# ep4ce30_c.net
KiCad netlist of a schematic drawn in Altium Designer
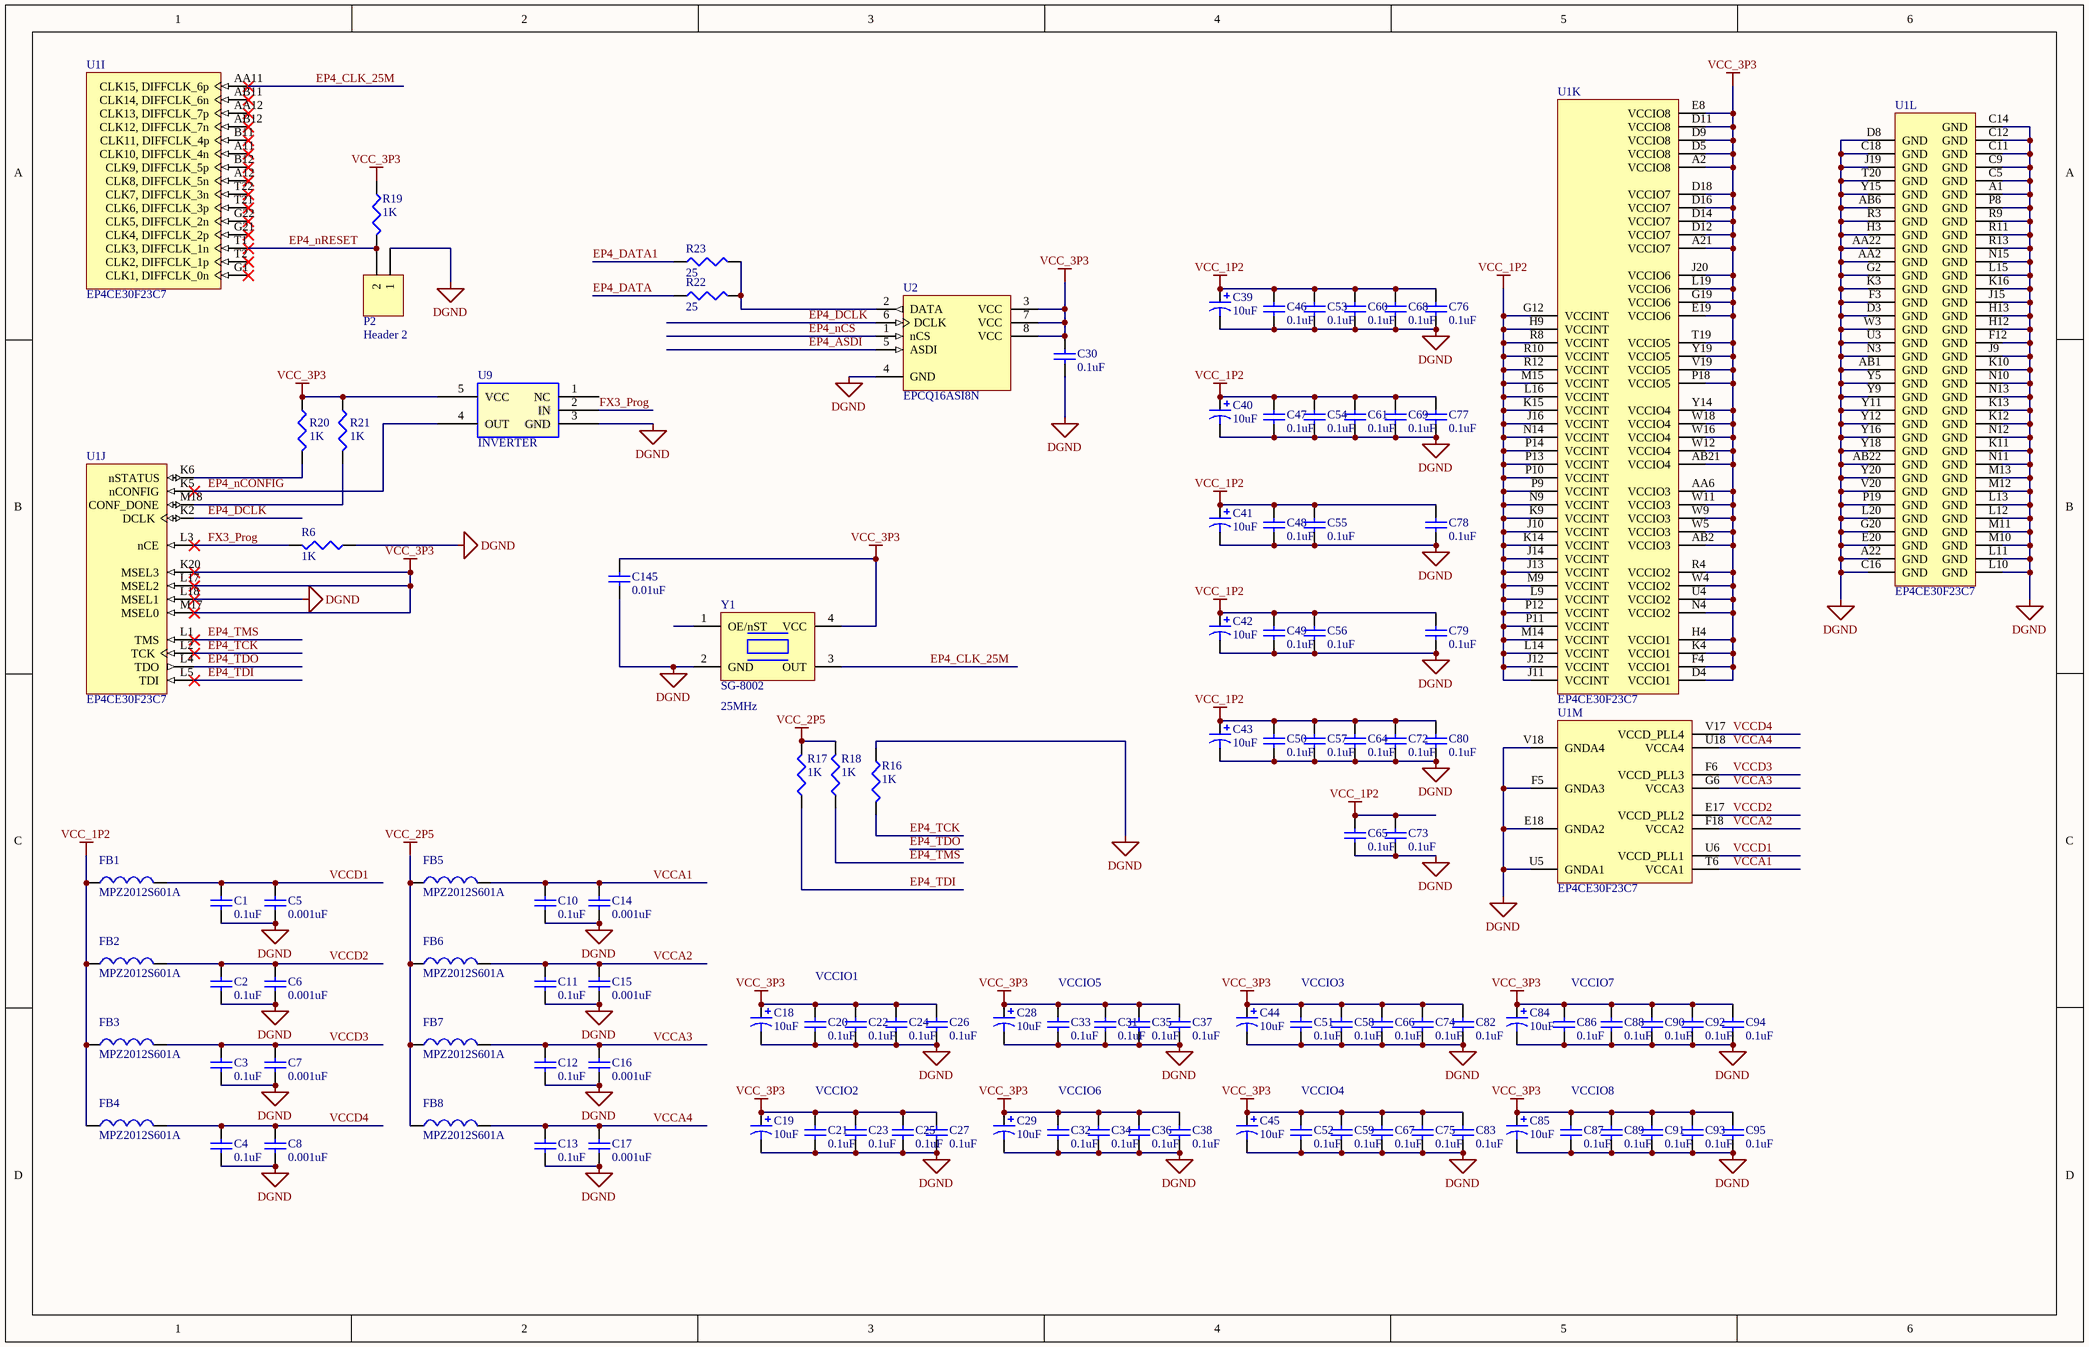
[diagram p0: ep4ce30_c.SchDoc]

(export (version "E")
  (design (tool "Eeschema 10.0.6"))
  (components
    (comp (ref "C1")
      (value "0.1uF")
      (footprint "C_0402")
      (description "Capacitor (Semiconductor SIM Model)")
      (fields (field (name "Comment") "Capacitor") (field (name "PUBLISHER") "Altium Limited"))
      (libsource (lib "Miscellaneous Devices") (part "Cap Semi"))
    )
    (comp (ref "C2")
      (value "0.1uF")
      (footprint "C_0402")
      (description "Capacitor (Semiconductor SIM Model)")
      (fields (field (name "Comment") "Capacitor") (field (name "PUBLISHER") "Altium Limited"))
      (libsource (lib "Miscellaneous Devices") (part "Cap Semi"))
    )
    (comp (ref "C3")
      (value "0.1uF")
      (footprint "C_0402")
      (description "Capacitor (Semiconductor SIM Model)")
      (fields (field (name "Comment") "Capacitor") (field (name "PUBLISHER") "Altium Limited"))
      (libsource (lib "Miscellaneous Devices") (part "Cap Semi"))
    )
    (comp (ref "C4")
      (value "0.1uF")
      (footprint "C_0402")
      (description "Capacitor (Semiconductor SIM Model)")
      (fields (field (name "Comment") "Capacitor") (field (name "PUBLISHER") "Altium Limited"))
      (libsource (lib "Miscellaneous Devices") (part "Cap Semi"))
    )
    (comp (ref "C5")
      (value "0.001uF")
      (footprint "C_0402")
      (description "Capacitor (Semiconductor SIM Model)")
      (fields (field (name "Comment") "Capacitor") (field (name "PUBLISHER") "Altium Limited"))
      (libsource (lib "Miscellaneous Devices") (part "Cap Semi"))
    )
    (comp (ref "C6")
      (value "0.001uF")
      (footprint "C_0402")
      (description "Capacitor (Semiconductor SIM Model)")
      (fields (field (name "Comment") "Capacitor") (field (name "PUBLISHER") "Altium Limited"))
      (libsource (lib "Miscellaneous Devices") (part "Cap Semi"))
    )
    (comp (ref "C7")
      (value "0.001uF")
      (footprint "C_0402")
      (description "Capacitor (Semiconductor SIM Model)")
      (fields (field (name "Comment") "Capacitor") (field (name "PUBLISHER") "Altium Limited"))
      (libsource (lib "Miscellaneous Devices") (part "Cap Semi"))
    )
    (comp (ref "C8")
      (value "0.001uF")
      (footprint "C_0402")
      (description "Capacitor (Semiconductor SIM Model)")
      (fields (field (name "Comment") "Capacitor") (field (name "PUBLISHER") "Altium Limited"))
      (libsource (lib "Miscellaneous Devices") (part "Cap Semi"))
    )
    (comp (ref "C10")
      (value "0.1uF")
      (footprint "C_0402")
      (description "Capacitor (Semiconductor SIM Model)")
      (fields (field (name "Comment") "Capacitor") (field (name "PUBLISHER") "Altium Limited"))
      (libsource (lib "Miscellaneous Devices") (part "Cap Semi"))
    )
    (comp (ref "C11")
      (value "0.1uF")
      (footprint "C_0402")
      (description "Capacitor (Semiconductor SIM Model)")
      (fields (field (name "Comment") "Capacitor") (field (name "PUBLISHER") "Altium Limited"))
      (libsource (lib "Miscellaneous Devices") (part "Cap Semi"))
    )
    (comp (ref "C12")
      (value "0.1uF")
      (footprint "C_0402")
      (description "Capacitor (Semiconductor SIM Model)")
      (fields (field (name "Comment") "Capacitor") (field (name "PUBLISHER") "Altium Limited"))
      (libsource (lib "Miscellaneous Devices") (part "Cap Semi"))
    )
    (comp (ref "C13")
      (value "0.1uF")
      (footprint "C_0402")
      (description "Capacitor (Semiconductor SIM Model)")
      (fields (field (name "Comment") "Capacitor") (field (name "PUBLISHER") "Altium Limited"))
      (libsource (lib "Miscellaneous Devices") (part "Cap Semi"))
    )
    (comp (ref "C14")
      (value "0.001uF")
      (footprint "C_0402")
      (description "Capacitor (Semiconductor SIM Model)")
      (fields (field (name "Comment") "Capacitor") (field (name "PUBLISHER") "Altium Limited"))
      (libsource (lib "Miscellaneous Devices") (part "Cap Semi"))
    )
    (comp (ref "C15")
      (value "0.001uF")
      (footprint "C_0402")
      (description "Capacitor (Semiconductor SIM Model)")
      (fields (field (name "Comment") "Capacitor") (field (name "PUBLISHER") "Altium Limited"))
      (libsource (lib "Miscellaneous Devices") (part "Cap Semi"))
    )
    (comp (ref "C16")
      (value "0.001uF")
      (footprint "C_0402")
      (description "Capacitor (Semiconductor SIM Model)")
      (fields (field (name "Comment") "Capacitor") (field (name "PUBLISHER") "Altium Limited"))
      (libsource (lib "Miscellaneous Devices") (part "Cap Semi"))
    )
    (comp (ref "C17")
      (value "0.001uF")
      (footprint "C_0402")
      (description "Capacitor (Semiconductor SIM Model)")
      (fields (field (name "Comment") "Capacitor") (field (name "PUBLISHER") "Altium Limited"))
      (libsource (lib "Miscellaneous Devices") (part "Cap Semi"))
    )
    (comp (ref "C18")
      (value "10uF")
      (footprint "CAP_B")
      (description "Polarized Capacitor (Surface Mount)")
      (fields (field (name "Comment") "Polarized Capacitor") (field (name "PUBLISHER") "Altium Limited"))
      (libsource (lib "Miscellaneous Devices") (part "Cap Pol3"))
    )
    (comp (ref "C19")
      (value "10uF")
      (footprint "CAP_B")
      (description "Polarized Capacitor (Surface Mount)")
      (fields (field (name "Comment") "Polarized Capacitor") (field (name "PUBLISHER") "Altium Limited"))
      (libsource (lib "Miscellaneous Devices") (part "Cap Pol3"))
    )
    (comp (ref "C20")
      (value "0.1uF")
      (footprint "C_0402")
      (description "Capacitor (Semiconductor SIM Model)")
      (fields (field (name "Comment") "Capacitor") (field (name "PUBLISHER") "Altium Limited"))
      (libsource (lib "Miscellaneous Devices") (part "Cap Semi"))
    )
    (comp (ref "C21")
      (value "0.1uF")
      (footprint "C_0402")
      (description "Capacitor (Semiconductor SIM Model)")
      (fields (field (name "Comment") "Capacitor") (field (name "PUBLISHER") "Altium Limited"))
      (libsource (lib "Miscellaneous Devices") (part "Cap Semi"))
    )
    (comp (ref "C22")
      (value "0.1uF")
      (footprint "C_0402")
      (description "Capacitor (Semiconductor SIM Model)")
      (fields (field (name "Comment") "Capacitor") (field (name "PUBLISHER") "Altium Limited"))
      (libsource (lib "Miscellaneous Devices") (part "Cap Semi"))
    )
    (comp (ref "C23")
      (value "0.1uF")
      (footprint "C_0402")
      (description "Capacitor (Semiconductor SIM Model)")
      (fields (field (name "Comment") "Capacitor") (field (name "PUBLISHER") "Altium Limited"))
      (libsource (lib "Miscellaneous Devices") (part "Cap Semi"))
    )
    (comp (ref "C24")
      (value "0.1uF")
      (footprint "C_0402")
      (description "Capacitor (Semiconductor SIM Model)")
      (fields (field (name "Comment") "Capacitor") (field (name "PUBLISHER") "Altium Limited"))
      (libsource (lib "Miscellaneous Devices") (part "Cap Semi"))
    )
    (comp (ref "C25")
      (value "0.1uF")
      (footprint "C_0402")
      (description "Capacitor (Semiconductor SIM Model)")
      (fields (field (name "Comment") "Capacitor") (field (name "PUBLISHER") "Altium Limited"))
      (libsource (lib "Miscellaneous Devices") (part "Cap Semi"))
    )
    (comp (ref "C26")
      (value "0.1uF")
      (footprint "C_0402")
      (description "Capacitor (Semiconductor SIM Model)")
      (fields (field (name "Comment") "Capacitor") (field (name "PUBLISHER") "Altium Limited"))
      (libsource (lib "Miscellaneous Devices") (part "Cap Semi"))
    )
    (comp (ref "C27")
      (value "0.1uF")
      (footprint "C_0402")
      (description "Capacitor (Semiconductor SIM Model)")
      (fields (field (name "Comment") "Capacitor") (field (name "PUBLISHER") "Altium Limited"))
      (libsource (lib "Miscellaneous Devices") (part "Cap Semi"))
    )
    (comp (ref "C28")
      (value "10uF")
      (footprint "CAP_B")
      (description "Polarized Capacitor (Surface Mount)")
      (fields (field (name "Comment") "Polarized Capacitor") (field (name "PUBLISHER") "Altium Limited"))
      (libsource (lib "Miscellaneous Devices") (part "Cap Pol3"))
    )
    (comp (ref "C29")
      (value "10uF")
      (footprint "CAP_B")
      (description "Polarized Capacitor (Surface Mount)")
      (fields (field (name "Comment") "Polarized Capacitor") (field (name "PUBLISHER") "Altium Limited"))
      (libsource (lib "Miscellaneous Devices") (part "Cap Pol3"))
    )
    (comp (ref "C30")
      (value "0.1uF")
      (footprint "C_0402")
      (description "Capacitor (Semiconductor SIM Model)")
      (fields (field (name "Comment") "Capacitor") (field (name "PUBLISHER") "Altium Limited"))
      (libsource (lib "Miscellaneous Devices") (part "Cap Semi"))
    )
    (comp (ref "C31")
      (value "0.1uF")
      (footprint "C_0402")
      (description "Capacitor (Semiconductor SIM Model)")
      (fields (field (name "Comment") "Capacitor") (field (name "PUBLISHER") "Altium Limited"))
      (libsource (lib "Miscellaneous Devices") (part "Cap Semi"))
    )
    (comp (ref "C32")
      (value "0.1uF")
      (footprint "C_0402")
      (description "Capacitor (Semiconductor SIM Model)")
      (fields (field (name "Comment") "Capacitor") (field (name "PUBLISHER") "Altium Limited"))
      (libsource (lib "Miscellaneous Devices") (part "Cap Semi"))
    )
    (comp (ref "C33")
      (value "0.1uF")
      (footprint "C_0402")
      (description "Capacitor (Semiconductor SIM Model)")
      (fields (field (name "Comment") "Capacitor") (field (name "PUBLISHER") "Altium Limited"))
      (libsource (lib "Miscellaneous Devices") (part "Cap Semi"))
    )
    (comp (ref "C34")
      (value "0.1uF")
      (footprint "C_0402")
      (description "Capacitor (Semiconductor SIM Model)")
      (fields (field (name "Comment") "Capacitor") (field (name "PUBLISHER") "Altium Limited"))
      (libsource (lib "Miscellaneous Devices") (part "Cap Semi"))
    )
    (comp (ref "C35")
      (value "0.1uF")
      (footprint "C_0402")
      (description "Capacitor (Semiconductor SIM Model)")
      (fields (field (name "Comment") "Capacitor") (field (name "PUBLISHER") "Altium Limited"))
      (libsource (lib "Miscellaneous Devices") (part "Cap Semi"))
    )
    (comp (ref "C36")
      (value "0.1uF")
      (footprint "C_0402")
      (description "Capacitor (Semiconductor SIM Model)")
      (fields (field (name "Comment") "Capacitor") (field (name "PUBLISHER") "Altium Limited"))
      (libsource (lib "Miscellaneous Devices") (part "Cap Semi"))
    )
    (comp (ref "C37")
      (value "0.1uF")
      (footprint "C_0402")
      (description "Capacitor (Semiconductor SIM Model)")
      (fields (field (name "Comment") "Capacitor") (field (name "PUBLISHER") "Altium Limited"))
      (libsource (lib "Miscellaneous Devices") (part "Cap Semi"))
    )
    (comp (ref "C38")
      (value "0.1uF")
      (footprint "C_0402")
      (description "Capacitor (Semiconductor SIM Model)")
      (fields (field (name "Comment") "Capacitor") (field (name "PUBLISHER") "Altium Limited"))
      (libsource (lib "Miscellaneous Devices") (part "Cap Semi"))
    )
    (comp (ref "C39")
      (value "10uF")
      (footprint "CAP_B")
      (description "Polarized Capacitor (Surface Mount)")
      (fields (field (name "Comment") "Polarized Capacitor") (field (name "PUBLISHER") "Altium Limited"))
      (libsource (lib "Miscellaneous Devices") (part "Cap Pol3"))
    )
    (comp (ref "C40")
      (value "10uF")
      (footprint "CAP_B")
      (description "Polarized Capacitor (Surface Mount)")
      (fields (field (name "Comment") "Polarized Capacitor") (field (name "PUBLISHER") "Altium Limited"))
      (libsource (lib "Miscellaneous Devices") (part "Cap Pol3"))
    )
    (comp (ref "C41")
      (value "10uF")
      (footprint "CAP_B")
      (description "Polarized Capacitor (Surface Mount)")
      (fields (field (name "Comment") "Polarized Capacitor") (field (name "PUBLISHER") "Altium Limited"))
      (libsource (lib "Miscellaneous Devices") (part "Cap Pol3"))
    )
    (comp (ref "C42")
      (value "10uF")
      (footprint "CAP_B")
      (description "Polarized Capacitor (Surface Mount)")
      (fields (field (name "Comment") "Polarized Capacitor") (field (name "PUBLISHER") "Altium Limited"))
      (libsource (lib "Miscellaneous Devices") (part "Cap Pol3"))
    )
    (comp (ref "C43")
      (value "10uF")
      (footprint "CAP_B")
      (description "Polarized Capacitor (Surface Mount)")
      (fields (field (name "Comment") "Polarized Capacitor") (field (name "PUBLISHER") "Altium Limited"))
      (libsource (lib "Miscellaneous Devices") (part "Cap Pol3"))
    )
    (comp (ref "C44")
      (value "10uF")
      (footprint "CAP_B")
      (description "Polarized Capacitor (Surface Mount)")
      (fields (field (name "Comment") "Polarized Capacitor") (field (name "PUBLISHER") "Altium Limited"))
      (libsource (lib "Miscellaneous Devices") (part "Cap Pol3"))
    )
    (comp (ref "C45")
      (value "10uF")
      (footprint "CAP_B")
      (description "Polarized Capacitor (Surface Mount)")
      (fields (field (name "Comment") "Polarized Capacitor") (field (name "PUBLISHER") "Altium Limited"))
      (libsource (lib "Miscellaneous Devices") (part "Cap Pol3"))
    )
    (comp (ref "C46")
      (value "0.1uF")
      (footprint "C_0402")
      (description "Capacitor (Semiconductor SIM Model)")
      (fields (field (name "Comment") "Capacitor") (field (name "PUBLISHER") "Altium Limited"))
      (libsource (lib "Miscellaneous Devices") (part "Cap Semi"))
    )
    (comp (ref "C47")
      (value "0.1uF")
      (footprint "C_0402")
      (description "Capacitor (Semiconductor SIM Model)")
      (fields (field (name "Comment") "Capacitor") (field (name "PUBLISHER") "Altium Limited"))
      (libsource (lib "Miscellaneous Devices") (part "Cap Semi"))
    )
    (comp (ref "C48")
      (value "0.1uF")
      (footprint "C_0402")
      (description "Capacitor (Semiconductor SIM Model)")
      (fields (field (name "Comment") "Capacitor") (field (name "PUBLISHER") "Altium Limited"))
      (libsource (lib "Miscellaneous Devices") (part "Cap Semi"))
    )
    (comp (ref "C49")
      (value "0.1uF")
      (footprint "C_0402")
      (description "Capacitor (Semiconductor SIM Model)")
      (fields (field (name "Comment") "Capacitor") (field (name "PUBLISHER") "Altium Limited"))
      (libsource (lib "Miscellaneous Devices") (part "Cap Semi"))
    )
    (comp (ref "C50")
      (value "0.1uF")
      (footprint "C_0402")
      (description "Capacitor (Semiconductor SIM Model)")
      (fields (field (name "Comment") "Capacitor") (field (name "PUBLISHER") "Altium Limited"))
      (libsource (lib "Miscellaneous Devices") (part "Cap Semi"))
    )
    (comp (ref "C51")
      (value "0.1uF")
      (footprint "C_0402")
      (description "Capacitor (Semiconductor SIM Model)")
      (fields (field (name "Comment") "Capacitor") (field (name "PUBLISHER") "Altium Limited"))
      (libsource (lib "Miscellaneous Devices") (part "Cap Semi"))
    )
    (comp (ref "C52")
      (value "0.1uF")
      (footprint "C_0402")
      (description "Capacitor (Semiconductor SIM Model)")
      (fields (field (name "Comment") "Capacitor") (field (name "PUBLISHER") "Altium Limited"))
      (libsource (lib "Miscellaneous Devices") (part "Cap Semi"))
    )
    (comp (ref "C53")
      (value "0.1uF")
      (footprint "C_0402")
      (description "Capacitor (Semiconductor SIM Model)")
      (fields (field (name "Comment") "Capacitor") (field (name "PUBLISHER") "Altium Limited"))
      (libsource (lib "Miscellaneous Devices") (part "Cap Semi"))
    )
    (comp (ref "C54")
      (value "0.1uF")
      (footprint "C_0402")
      (description "Capacitor (Semiconductor SIM Model)")
      (fields (field (name "Comment") "Capacitor") (field (name "PUBLISHER") "Altium Limited"))
      (libsource (lib "Miscellaneous Devices") (part "Cap Semi"))
    )
    (comp (ref "C55")
      (value "0.1uF")
      (footprint "C_0402")
      (description "Capacitor (Semiconductor SIM Model)")
      (fields (field (name "Comment") "Capacitor") (field (name "PUBLISHER") "Altium Limited"))
      (libsource (lib "Miscellaneous Devices") (part "Cap Semi"))
    )
    (comp (ref "C56")
      (value "0.1uF")
      (footprint "C_0402")
      (description "Capacitor (Semiconductor SIM Model)")
      (fields (field (name "Comment") "Capacitor") (field (name "PUBLISHER") "Altium Limited"))
      (libsource (lib "Miscellaneous Devices") (part "Cap Semi"))
    )
    (comp (ref "C57")
      (value "0.1uF")
      (footprint "C_0402")
      (description "Capacitor (Semiconductor SIM Model)")
      (fields (field (name "Comment") "Capacitor") (field (name "PUBLISHER") "Altium Limited"))
      (libsource (lib "Miscellaneous Devices") (part "Cap Semi"))
    )
    (comp (ref "C58")
      (value "0.1uF")
      (footprint "C_0402")
      (description "Capacitor (Semiconductor SIM Model)")
      (fields (field (name "Comment") "Capacitor") (field (name "PUBLISHER") "Altium Limited"))
      (libsource (lib "Miscellaneous Devices") (part "Cap Semi"))
    )
    (comp (ref "C59")
      (value "0.1uF")
      (footprint "C_0402")
      (description "Capacitor (Semiconductor SIM Model)")
      (fields (field (name "Comment") "Capacitor") (field (name "PUBLISHER") "Altium Limited"))
      (libsource (lib "Miscellaneous Devices") (part "Cap Semi"))
    )
    (comp (ref "C60")
      (value "0.1uF")
      (footprint "C_0402")
      (description "Capacitor (Semiconductor SIM Model)")
      (fields (field (name "Comment") "Capacitor") (field (name "PUBLISHER") "Altium Limited"))
      (libsource (lib "Miscellaneous Devices") (part "Cap Semi"))
    )
    (comp (ref "C61")
      (value "0.1uF")
      (footprint "C_0402")
      (description "Capacitor (Semiconductor SIM Model)")
      (fields (field (name "Comment") "Capacitor") (field (name "PUBLISHER") "Altium Limited"))
      (libsource (lib "Miscellaneous Devices") (part "Cap Semi"))
    )
    (comp (ref "C64")
      (value "0.1uF")
      (footprint "C_0402")
      (description "Capacitor (Semiconductor SIM Model)")
      (fields (field (name "Comment") "Capacitor") (field (name "PUBLISHER") "Altium Limited"))
      (libsource (lib "Miscellaneous Devices") (part "Cap Semi"))
    )
    (comp (ref "C65")
      (value "0.1uF")
      (footprint "C_0402")
      (description "Capacitor (Semiconductor SIM Model)")
      (fields (field (name "Comment") "Capacitor") (field (name "PUBLISHER") "Altium Limited"))
      (libsource (lib "Miscellaneous Devices") (part "Cap Semi"))
    )
    (comp (ref "C66")
      (value "0.1uF")
      (footprint "C_0402")
      (description "Capacitor (Semiconductor SIM Model)")
      (fields (field (name "Comment") "Capacitor") (field (name "PUBLISHER") "Altium Limited"))
      (libsource (lib "Miscellaneous Devices") (part "Cap Semi"))
    )
    (comp (ref "C67")
      (value "0.1uF")
      (footprint "C_0402")
      (description "Capacitor (Semiconductor SIM Model)")
      (fields (field (name "Comment") "Capacitor") (field (name "PUBLISHER") "Altium Limited"))
      (libsource (lib "Miscellaneous Devices") (part "Cap Semi"))
    )
    (comp (ref "C68")
      (value "0.1uF")
      (footprint "C_0402")
      (description "Capacitor (Semiconductor SIM Model)")
      (fields (field (name "Comment") "Capacitor") (field (name "PUBLISHER") "Altium Limited"))
      (libsource (lib "Miscellaneous Devices") (part "Cap Semi"))
    )
    (comp (ref "C69")
      (value "0.1uF")
      (footprint "C_0402")
      (description "Capacitor (Semiconductor SIM Model)")
      (fields (field (name "Comment") "Capacitor") (field (name "PUBLISHER") "Altium Limited"))
      (libsource (lib "Miscellaneous Devices") (part "Cap Semi"))
    )
    (comp (ref "C72")
      (value "0.1uF")
      (footprint "C_0402")
      (description "Capacitor (Semiconductor SIM Model)")
      (fields (field (name "Comment") "Capacitor") (field (name "PUBLISHER") "Altium Limited"))
      (libsource (lib "Miscellaneous Devices") (part "Cap Semi"))
    )
    (comp (ref "C73")
      (value "0.1uF")
      (footprint "C_0402")
      (description "Capacitor (Semiconductor SIM Model)")
      (fields (field (name "Comment") "Capacitor") (field (name "PUBLISHER") "Altium Limited"))
      (libsource (lib "Miscellaneous Devices") (part "Cap Semi"))
    )
    (comp (ref "C74")
      (value "0.1uF")
      (footprint "C_0402")
      (description "Capacitor (Semiconductor SIM Model)")
      (fields (field (name "Comment") "Capacitor") (field (name "PUBLISHER") "Altium Limited"))
      (libsource (lib "Miscellaneous Devices") (part "Cap Semi"))
    )
    (comp (ref "C75")
      (value "0.1uF")
      (footprint "C_0402")
      (description "Capacitor (Semiconductor SIM Model)")
      (fields (field (name "Comment") "Capacitor") (field (name "PUBLISHER") "Altium Limited"))
      (libsource (lib "Miscellaneous Devices") (part "Cap Semi"))
    )
    (comp (ref "C76")
      (value "0.1uF")
      (footprint "C_0402")
      (description "Capacitor (Semiconductor SIM Model)")
      (fields (field (name "Comment") "Capacitor") (field (name "PUBLISHER") "Altium Limited"))
      (libsource (lib "Miscellaneous Devices") (part "Cap Semi"))
    )
    (comp (ref "C77")
      (value "0.1uF")
      (footprint "C_0402")
      (description "Capacitor (Semiconductor SIM Model)")
      (fields (field (name "Comment") "Capacitor") (field (name "PUBLISHER") "Altium Limited"))
      (libsource (lib "Miscellaneous Devices") (part "Cap Semi"))
    )
    (comp (ref "C78")
      (value "0.1uF")
      (footprint "C_0402")
      (description "Capacitor (Semiconductor SIM Model)")
      (fields (field (name "Comment") "Capacitor") (field (name "PUBLISHER") "Altium Limited"))
      (libsource (lib "Miscellaneous Devices") (part "Cap Semi"))
    )
    (comp (ref "C79")
      (value "0.1uF")
      (footprint "C_0402")
      (description "Capacitor (Semiconductor SIM Model)")
      (fields (field (name "Comment") "Capacitor") (field (name "PUBLISHER") "Altium Limited"))
      (libsource (lib "Miscellaneous Devices") (part "Cap Semi"))
    )
    (comp (ref "C80")
      (value "0.1uF")
      (footprint "C_0402")
      (description "Capacitor (Semiconductor SIM Model)")
      (fields (field (name "Comment") "Capacitor") (field (name "PUBLISHER") "Altium Limited"))
      (libsource (lib "Miscellaneous Devices") (part "Cap Semi"))
    )
    (comp (ref "C82")
      (value "0.1uF")
      (footprint "C_0402")
      (description "Capacitor (Semiconductor SIM Model)")
      (fields (field (name "Comment") "Capacitor") (field (name "PUBLISHER") "Altium Limited"))
      (libsource (lib "Miscellaneous Devices") (part "Cap Semi"))
    )
    (comp (ref "C83")
      (value "0.1uF")
      (footprint "C_0402")
      (description "Capacitor (Semiconductor SIM Model)")
      (fields (field (name "Comment") "Capacitor") (field (name "PUBLISHER") "Altium Limited"))
      (libsource (lib "Miscellaneous Devices") (part "Cap Semi"))
    )
    (comp (ref "C84")
      (value "10uF")
      (footprint "CAP_B")
      (description "Polarized Capacitor (Surface Mount)")
      (fields (field (name "Comment") "Polarized Capacitor") (field (name "PUBLISHER") "Altium Limited"))
      (libsource (lib "Miscellaneous Devices") (part "Cap Pol3"))
    )
    (comp (ref "C85")
      (value "10uF")
      (footprint "CAP_B")
      (description "Polarized Capacitor (Surface Mount)")
      (fields (field (name "Comment") "Polarized Capacitor") (field (name "PUBLISHER") "Altium Limited"))
      (libsource (lib "Miscellaneous Devices") (part "Cap Pol3"))
    )
    (comp (ref "C86")
      (value "0.1uF")
      (footprint "C_0402")
      (description "Capacitor (Semiconductor SIM Model)")
      (fields (field (name "Comment") "Capacitor") (field (name "PUBLISHER") "Altium Limited"))
      (libsource (lib "Miscellaneous Devices") (part "Cap Semi"))
    )
    (comp (ref "C87")
      (value "0.1uF")
      (footprint "C_0402")
      (description "Capacitor (Semiconductor SIM Model)")
      (fields (field (name "Comment") "Capacitor") (field (name "PUBLISHER") "Altium Limited"))
      (libsource (lib "Miscellaneous Devices") (part "Cap Semi"))
    )
    (comp (ref "C88")
      (value "0.1uF")
      (footprint "C_0402")
      (description "Capacitor (Semiconductor SIM Model)")
      (fields (field (name "Comment") "Capacitor") (field (name "PUBLISHER") "Altium Limited"))
      (libsource (lib "Miscellaneous Devices") (part "Cap Semi"))
    )
    (comp (ref "C89")
      (value "0.1uF")
      (footprint "C_0402")
      (description "Capacitor (Semiconductor SIM Model)")
      (fields (field (name "Comment") "Capacitor") (field (name "PUBLISHER") "Altium Limited"))
      (libsource (lib "Miscellaneous Devices") (part "Cap Semi"))
    )
    (comp (ref "C90")
      (value "0.1uF")
      (footprint "C_0402")
      (description "Capacitor (Semiconductor SIM Model)")
      (fields (field (name "Comment") "Capacitor") (field (name "PUBLISHER") "Altium Limited"))
      (libsource (lib "Miscellaneous Devices") (part "Cap Semi"))
    )
    (comp (ref "C91")
      (value "0.1uF")
      (footprint "C_0402")
      (description "Capacitor (Semiconductor SIM Model)")
      (fields (field (name "Comment") "Capacitor") (field (name "PUBLISHER") "Altium Limited"))
      (libsource (lib "Miscellaneous Devices") (part "Cap Semi"))
    )
    (comp (ref "C92")
      (value "0.1uF")
      (footprint "C_0402")
      (description "Capacitor (Semiconductor SIM Model)")
      (fields (field (name "Comment") "Capacitor") (field (name "PUBLISHER") "Altium Limited"))
      (libsource (lib "Miscellaneous Devices") (part "Cap Semi"))
    )
    (comp (ref "C93")
      (value "0.1uF")
      (footprint "C_0402")
      (description "Capacitor (Semiconductor SIM Model)")
      (fields (field (name "Comment") "Capacitor") (field (name "PUBLISHER") "Altium Limited"))
      (libsource (lib "Miscellaneous Devices") (part "Cap Semi"))
    )
    (comp (ref "C94")
      (value "0.1uF")
      (footprint "C_0402")
      (description "Capacitor (Semiconductor SIM Model)")
      (fields (field (name "Comment") "Capacitor") (field (name "PUBLISHER") "Altium Limited"))
      (libsource (lib "Miscellaneous Devices") (part "Cap Semi"))
    )
    (comp (ref "C95")
      (value "0.1uF")
      (footprint "C_0402")
      (description "Capacitor (Semiconductor SIM Model)")
      (fields (field (name "Comment") "Capacitor") (field (name "PUBLISHER") "Altium Limited"))
      (libsource (lib "Miscellaneous Devices") (part "Cap Semi"))
    )
    (comp (ref "C145")
      (value "0.01uF")
      (footprint "C_0402")
      (description "Capacitor (Semiconductor SIM Model)")
      (fields (field (name "Comment") "Capacitor") (field (name "PUBLISHER") "Altium Limited"))
      (libsource (lib "Miscellaneous Devices") (part "Cap Semi"))
    )
    (comp (ref "FB1")
      (value "MPZ2012S601A")
      (footprint "SMD_0805")
      (description "MPZ2012X")
      (libsource (lib "clc_ad_pro") (part "MPZ2012X"))
    )
    (comp (ref "FB2")
      (value "MPZ2012S601A")
      (footprint "SMD_0805")
      (description "MPZ2012X")
      (libsource (lib "clc_ad_pro") (part "MPZ2012X"))
    )
    (comp (ref "FB3")
      (value "MPZ2012S601A")
      (footprint "SMD_0805")
      (description "MPZ2012X")
      (libsource (lib "clc_ad_pro") (part "MPZ2012X"))
    )
    (comp (ref "FB4")
      (value "MPZ2012S601A")
      (footprint "SMD_0805")
      (description "MPZ2012X")
      (libsource (lib "clc_ad_pro") (part "MPZ2012X"))
    )
    (comp (ref "FB5")
      (value "MPZ2012S601A")
      (footprint "SMD_0805")
      (description "MPZ2012X")
      (libsource (lib "clc_ad_pro") (part "MPZ2012X"))
    )
    (comp (ref "FB6")
      (value "MPZ2012S601A")
      (footprint "SMD_0805")
      (description "MPZ2012X")
      (libsource (lib "clc_ad_pro") (part "MPZ2012X"))
    )
    (comp (ref "FB7")
      (value "MPZ2012S601A")
      (footprint "SMD_0805")
      (description "MPZ2012X")
      (libsource (lib "clc_ad_pro") (part "MPZ2012X"))
    )
    (comp (ref "FB8")
      (value "MPZ2012S601A")
      (footprint "SMD_0805")
      (description "MPZ2012X")
      (libsource (lib "clc_ad_pro") (part "MPZ2012X"))
    )
    (comp (ref "P2")
      (value "Header 2")
      (footprint "HDR1X2")
      (description "Header, 2-Pin")
      (fields (field (name "PUBLISHER") "Altium Limited"))
      (libsource (lib "Miscellaneous Connectors") (part "Header 2"))
    )
    (comp (ref "R6")
      (value "1K")
      (footprint "J1-0603")
      (description "Resistor")
      (fields (field (name "PUBLISHER") "Altium Limited"))
      (libsource (lib "Miscellaneous Devices") (part "Res3"))
    )
    (comp (ref "R16")
      (value "1K")
      (footprint "J1-0603")
      (description "Resistor")
      (fields (field (name "PUBLISHER") "Altium Limited"))
      (libsource (lib "Miscellaneous Devices") (part "Res3"))
    )
    (comp (ref "R17")
      (value "1K")
      (footprint "J1-0603")
      (description "Resistor")
      (fields (field (name "PUBLISHER") "Altium Limited"))
      (libsource (lib "Miscellaneous Devices") (part "Res3"))
    )
    (comp (ref "R18")
      (value "1K")
      (footprint "J1-0603")
      (description "Resistor")
      (fields (field (name "PUBLISHER") "Altium Limited"))
      (libsource (lib "Miscellaneous Devices") (part "Res3"))
    )
    (comp (ref "R19")
      (value "1K")
      (footprint "J1-0603")
      (description "Resistor")
      (fields (field (name "PUBLISHER") "Altium Limited"))
      (libsource (lib "Miscellaneous Devices") (part "Res3"))
    )
    (comp (ref "R20")
      (value "1K")
      (footprint "J1-0603")
      (description "Resistor")
      (fields (field (name "PUBLISHER") "Altium Limited"))
      (libsource (lib "Miscellaneous Devices") (part "Res3"))
    )
    (comp (ref "R21")
      (value "1K")
      (footprint "J1-0603")
      (description "Resistor")
      (fields (field (name "PUBLISHER") "Altium Limited"))
      (libsource (lib "Miscellaneous Devices") (part "Res3"))
    )
    (comp (ref "R22")
      (value "25")
      (footprint "J1-0603")
      (description "Resistor")
      (fields (field (name "PUBLISHER") "Altium Limited"))
      (libsource (lib "Miscellaneous Devices") (part "Res3"))
    )
    (comp (ref "R23")
      (value "25")
      (footprint "J1-0603")
      (description "Resistor")
      (fields (field (name "PUBLISHER") "Altium Limited"))
      (libsource (lib "Miscellaneous Devices") (part "Res3"))
    )
    (comp (ref "U1")
      (value "EP4CE30F23C7")
      (footprint "FBGA484_A-240")
      (fields (field (name "MANUFACTURER") "Altera"))
      (libsource (lib "Altera Cyclone IV E") (part "EP4CE30F23C7"))
    )
    (comp (ref "U2")
      (value "EPCQ16ASI8N")
      (footprint "SOIC8_N")
      (fields (field (name "PUBLISHER") "Altium Limited"))
      (libsource (lib "Altera EPCS Configuration Device") (part "EPCS4SI8N"))
    )
    (comp (ref "U9")
      (value "INVERTER")
      (footprint "TC7SET08FU")
      (libsource (lib "auxiliarylib1") (part "INVERTER"))
    )
    (comp (ref "Y1")
      (value "SG-8002")
      (footprint "SON_4")
      (description "OSC XO CMOS SMD")
      (libsource (lib "apex_usb_v2") (part "SG-8002"))
    )
  )
  (nets
    (net (code "1") (name "/EP4_ASDI") (class "Default")
      (node (ref "U2") (pin "5") (pinfunction "ASDI_5") (pintype "input"))
    )
    (net (code "2") (name "/EP4_CLK_25M") (class "Default")
      (node (ref "U1") (pin "AA11") (pinfunction "CLK15,_DIFFCLK_6p_AA11") (pintype "input"))
      (node (ref "Y1") (pin "3") (pinfunction "OUT_3") (pintype "passive"))
    )
    (net (code "3") (name "/EP4_DATA") (class "Default")
      (node (ref "R22") (pin "1") (pinfunction "1_1") (pintype "passive"))
    )
    (net (code "4") (name "/EP4_DATA1") (class "Default")
      (node (ref "R23") (pin "1") (pinfunction "1_1") (pintype "passive"))
    )
    (net (code "5") (name "/EP4_DCLK") (class "Default")
      (node (ref "U1") (pin "K2") (pinfunction "DCLK_K2") (pintype "bidirectional"))
      (node (ref "U2") (pin "6") (pinfunction "DCLK_6") (pintype "input"))
    )
    (net (code "6") (name "/EP4_TCK") (class "Default")
      (node (ref "R16") (pin "2") (pinfunction "2_2") (pintype "passive"))
      (node (ref "U1") (pin "L2") (pinfunction "TCK_L2") (pintype "input"))
    )
    (net (code "7") (name "/EP4_TDI") (class "Default")
      (node (ref "R17") (pin "1") (pinfunction "1_1") (pintype "passive"))
      (node (ref "U1") (pin "L5") (pinfunction "TDI_L5") (pintype "input"))
    )
    (net (code "8") (name "/EP4_TDO") (class "Default")
      (node (ref "U1") (pin "L4") (pinfunction "TDO_L4") (pintype "output"))
    )
    (net (code "9") (name "/EP4_TMS") (class "Default")
      (node (ref "R18") (pin "1") (pinfunction "1_1") (pintype "passive"))
      (node (ref "U1") (pin "L1") (pinfunction "TMS_L1") (pintype "input"))
    )
    (net (code "10") (name "/EP4_nCONFIG") (class "Default")
      (node (ref "U1") (pin "K5") (pinfunction "nCONFIG_K5") (pintype "input"))
      (node (ref "U9") (pin "4") (pinfunction "OUT_4") (pintype "passive"))
    )
    (net (code "11") (name "/EP4_nCS") (class "Default")
      (node (ref "U2") (pin "1") (pinfunction "nCS_1") (pintype "input"))
    )
    (net (code "12") (name "/EP4_nRESET") (class "Default")
      (node (ref "P2") (pin "2") (pinfunction "2_2") (pintype "passive"))
      (node (ref "R19") (pin "2") (pinfunction "2_2") (pintype "passive"))
      (node (ref "U1") (pin "T1") (pinfunction "CLK3,_DIFFCLK_1n_T1") (pintype "input"))
    )
    (net (code "13") (name "/FX3_Prog") (class "Default")
      (node (ref "R6") (pin "2") (pinfunction "2_2") (pintype "passive"))
      (node (ref "U1") (pin "L3") (pinfunction "nCE_L3") (pintype "input"))
      (node (ref "U9") (pin "2") (pinfunction "IN_2") (pintype "passive"))
    )
    (net (code "14") (name "/VCCA1") (class "Default")
      (node (ref "C10") (pin "2") (pinfunction "2_2") (pintype "passive"))
      (node (ref "C14") (pin "1") (pinfunction "1_1") (pintype "passive"))
      (node (ref "FB5") (pin "2") (pinfunction "2_2") (pintype "passive"))
      (node (ref "U1") (pin "T6") (pinfunction "VCCA1_T6") (pintype "power_in"))
    )
    (net (code "15") (name "/VCCA2") (class "Default")
      (node (ref "C11") (pin "2") (pinfunction "2_2") (pintype "passive"))
      (node (ref "C15") (pin "1") (pinfunction "1_1") (pintype "passive"))
      (node (ref "FB6") (pin "2") (pinfunction "2_2") (pintype "passive"))
      (node (ref "U1") (pin "F18") (pinfunction "VCCA2_F18") (pintype "power_in"))
    )
    (net (code "16") (name "/VCCA3") (class "Default")
      (node (ref "C12") (pin "2") (pinfunction "2_2") (pintype "passive"))
      (node (ref "C16") (pin "1") (pinfunction "1_1") (pintype "passive"))
      (node (ref "FB7") (pin "2") (pinfunction "2_2") (pintype "passive"))
      (node (ref "U1") (pin "G6") (pinfunction "VCCA3_G6") (pintype "power_in"))
    )
    (net (code "17") (name "/VCCA4") (class "Default")
      (node (ref "C13") (pin "2") (pinfunction "2_2") (pintype "passive"))
      (node (ref "C17") (pin "1") (pinfunction "1_1") (pintype "passive"))
      (node (ref "FB8") (pin "2") (pinfunction "2_2") (pintype "passive"))
      (node (ref "U1") (pin "U18") (pinfunction "VCCA4_U18") (pintype "power_in"))
    )
    (net (code "18") (name "/VCCD1") (class "Default")
      (node (ref "C1") (pin "1") (pinfunction "1_1") (pintype "passive"))
      (node (ref "C5") (pin "1") (pinfunction "1_1") (pintype "passive"))
      (node (ref "FB1") (pin "2") (pinfunction "2_2") (pintype "passive"))
      (node (ref "U1") (pin "U6") (pinfunction "VCCD_PLL1_U6") (pintype "power_in"))
    )
    (net (code "19") (name "/VCCD2") (class "Default")
      (node (ref "C2") (pin "1") (pinfunction "1_1") (pintype "passive"))
      (node (ref "C6") (pin "1") (pinfunction "1_1") (pintype "passive"))
      (node (ref "FB2") (pin "2") (pinfunction "2_2") (pintype "passive"))
      (node (ref "U1") (pin "E17") (pinfunction "VCCD_PLL2_E17") (pintype "power_in"))
    )
    (net (code "20") (name "/VCCD3") (class "Default")
      (node (ref "C3") (pin "1") (pinfunction "1_1") (pintype "passive"))
      (node (ref "C7") (pin "1") (pinfunction "1_1") (pintype "passive"))
      (node (ref "FB3") (pin "2") (pinfunction "2_2") (pintype "passive"))
      (node (ref "U1") (pin "F6") (pinfunction "VCCD_PLL3_F6") (pintype "power_in"))
    )
    (net (code "21") (name "/VCCD4") (class "Default")
      (node (ref "C4") (pin "2") (pinfunction "2_2") (pintype "passive"))
      (node (ref "C8") (pin "1") (pinfunction "1_1") (pintype "passive"))
      (node (ref "FB4") (pin "2") (pinfunction "2_2") (pintype "passive"))
      (node (ref "U1") (pin "V17") (pinfunction "VCCD_PLL4_V17") (pintype "power_in"))
    )
    (net (code "22") (name "DGND") (class "Default")
      (node (ref "C1") (pin "2") (pinfunction "2_2") (pintype "passive"))
      (node (ref "C10") (pin "1") (pinfunction "1_1") (pintype "passive"))
      (node (ref "C11") (pin "1") (pinfunction "1_1") (pintype "passive"))
      (node (ref "C12") (pin "1") (pinfunction "1_1") (pintype "passive"))
      (node (ref "C13") (pin "1") (pinfunction "1_1") (pintype "passive"))
      (node (ref "C14") (pin "2") (pinfunction "2_2") (pintype "passive"))
      (node (ref "C145") (pin "2") (pinfunction "2_2") (pintype "passive"))
      (node (ref "C15") (pin "2") (pinfunction "2_2") (pintype "passive"))
      (node (ref "C16") (pin "2") (pinfunction "2_2") (pintype "passive"))
      (node (ref "C17") (pin "2") (pinfunction "2_2") (pintype "passive"))
      (node (ref "C18") (pin "2") (pinfunction "2_2") (pintype "passive"))
      (node (ref "C19") (pin "2") (pinfunction "2_2") (pintype "passive"))
      (node (ref "C2") (pin "2") (pinfunction "2_2") (pintype "passive"))
      (node (ref "C20") (pin "2") (pinfunction "2_2") (pintype "passive"))
      (node (ref "C21") (pin "2") (pinfunction "2_2") (pintype "passive"))
      (node (ref "C22") (pin "2") (pinfunction "2_2") (pintype "passive"))
      (node (ref "C23") (pin "2") (pinfunction "2_2") (pintype "passive"))
      (node (ref "C24") (pin "2") (pinfunction "2_2") (pintype "passive"))
      (node (ref "C25") (pin "2") (pinfunction "2_2") (pintype "passive"))
      (node (ref "C26") (pin "2") (pinfunction "2_2") (pintype "passive"))
      (node (ref "C27") (pin "2") (pinfunction "2_2") (pintype "passive"))
      (node (ref "C28") (pin "2") (pinfunction "2_2") (pintype "passive"))
      (node (ref "C29") (pin "2") (pinfunction "2_2") (pintype "passive"))
      (node (ref "C3") (pin "2") (pinfunction "2_2") (pintype "passive"))
      (node (ref "C30") (pin "2") (pinfunction "2_2") (pintype "passive"))
      (node (ref "C31") (pin "2") (pinfunction "2_2") (pintype "passive"))
      (node (ref "C32") (pin "2") (pinfunction "2_2") (pintype "passive"))
      (node (ref "C33") (pin "2") (pinfunction "2_2") (pintype "passive"))
      (node (ref "C34") (pin "2") (pinfunction "2_2") (pintype "passive"))
      (node (ref "C35") (pin "2") (pinfunction "2_2") (pintype "passive"))
      (node (ref "C36") (pin "2") (pinfunction "2_2") (pintype "passive"))
      (node (ref "C37") (pin "2") (pinfunction "2_2") (pintype "passive"))
      (node (ref "C38") (pin "2") (pinfunction "2_2") (pintype "passive"))
      (node (ref "C39") (pin "2") (pinfunction "2_2") (pintype "passive"))
      (node (ref "C4") (pin "1") (pinfunction "1_1") (pintype "passive"))
      (node (ref "C40") (pin "2") (pinfunction "2_2") (pintype "passive"))
      (node (ref "C41") (pin "2") (pinfunction "2_2") (pintype "passive"))
      (node (ref "C42") (pin "2") (pinfunction "2_2") (pintype "passive"))
      (node (ref "C43") (pin "2") (pinfunction "2_2") (pintype "passive"))
      (node (ref "C44") (pin "2") (pinfunction "2_2") (pintype "passive"))
      (node (ref "C45") (pin "2") (pinfunction "2_2") (pintype "passive"))
      (node (ref "C46") (pin "2") (pinfunction "2_2") (pintype "passive"))
      (node (ref "C47") (pin "2") (pinfunction "2_2") (pintype "passive"))
      (node (ref "C48") (pin "2") (pinfunction "2_2") (pintype "passive"))
      (node (ref "C49") (pin "2") (pinfunction "2_2") (pintype "passive"))
      (node (ref "C5") (pin "2") (pinfunction "2_2") (pintype "passive"))
      (node (ref "C50") (pin "2") (pinfunction "2_2") (pintype "passive"))
      (node (ref "C51") (pin "2") (pinfunction "2_2") (pintype "passive"))
      (node (ref "C52") (pin "2") (pinfunction "2_2") (pintype "passive"))
      (node (ref "C53") (pin "2") (pinfunction "2_2") (pintype "passive"))
      (node (ref "C54") (pin "2") (pinfunction "2_2") (pintype "passive"))
      (node (ref "C55") (pin "2") (pinfunction "2_2") (pintype "passive"))
      (node (ref "C56") (pin "2") (pinfunction "2_2") (pintype "passive"))
      (node (ref "C57") (pin "2") (pinfunction "2_2") (pintype "passive"))
      (node (ref "C58") (pin "2") (pinfunction "2_2") (pintype "passive"))
      (node (ref "C59") (pin "2") (pinfunction "2_2") (pintype "passive"))
      (node (ref "C6") (pin "2") (pinfunction "2_2") (pintype "passive"))
      (node (ref "C60") (pin "2") (pinfunction "2_2") (pintype "passive"))
      (node (ref "C61") (pin "2") (pinfunction "2_2") (pintype "passive"))
      (node (ref "C64") (pin "2") (pinfunction "2_2") (pintype "passive"))
      (node (ref "C65") (pin "2") (pinfunction "2_2") (pintype "passive"))
      (node (ref "C66") (pin "2") (pinfunction "2_2") (pintype "passive"))
      (node (ref "C67") (pin "2") (pinfunction "2_2") (pintype "passive"))
      (node (ref "C68") (pin "2") (pinfunction "2_2") (pintype "passive"))
      (node (ref "C69") (pin "2") (pinfunction "2_2") (pintype "passive"))
      (node (ref "C7") (pin "2") (pinfunction "2_2") (pintype "passive"))
      (node (ref "C72") (pin "2") (pinfunction "2_2") (pintype "passive"))
      (node (ref "C73") (pin "2") (pinfunction "2_2") (pintype "passive"))
      (node (ref "C74") (pin "2") (pinfunction "2_2") (pintype "passive"))
      (node (ref "C75") (pin "2") (pinfunction "2_2") (pintype "passive"))
      (node (ref "C76") (pin "2") (pinfunction "2_2") (pintype "passive"))
      (node (ref "C77") (pin "2") (pinfunction "2_2") (pintype "passive"))
      (node (ref "C78") (pin "2") (pinfunction "2_2") (pintype "passive"))
      (node (ref "C79") (pin "2") (pinfunction "2_2") (pintype "passive"))
      (node (ref "C8") (pin "2") (pinfunction "2_2") (pintype "passive"))
      (node (ref "C80") (pin "2") (pinfunction "2_2") (pintype "passive"))
      (node (ref "C82") (pin "2") (pinfunction "2_2") (pintype "passive"))
      (node (ref "C83") (pin "2") (pinfunction "2_2") (pintype "passive"))
      (node (ref "C84") (pin "2") (pinfunction "2_2") (pintype "passive"))
      (node (ref "C85") (pin "2") (pinfunction "2_2") (pintype "passive"))
      (node (ref "C86") (pin "2") (pinfunction "2_2") (pintype "passive"))
      (node (ref "C87") (pin "2") (pinfunction "2_2") (pintype "passive"))
      (node (ref "C88") (pin "2") (pinfunction "2_2") (pintype "passive"))
      (node (ref "C89") (pin "2") (pinfunction "2_2") (pintype "passive"))
      (node (ref "C90") (pin "2") (pinfunction "2_2") (pintype "passive"))
      (node (ref "C91") (pin "2") (pinfunction "2_2") (pintype "passive"))
      (node (ref "C92") (pin "2") (pinfunction "2_2") (pintype "passive"))
      (node (ref "C93") (pin "2") (pinfunction "2_2") (pintype "passive"))
      (node (ref "C94") (pin "2") (pinfunction "2_2") (pintype "passive"))
      (node (ref "C95") (pin "2") (pinfunction "2_2") (pintype "passive"))
      (node (ref "P2") (pin "1") (pinfunction "1_1") (pintype "passive"))
      (node (ref "R16") (pin "1") (pinfunction "1_1") (pintype "passive"))
      (node (ref "R6") (pin "1") (pinfunction "1_1") (pintype "passive"))
      (node (ref "U1") (pin "A1") (pinfunction "GND_A1") (pintype "power_in"))
      (node (ref "U1") (pin "A22") (pinfunction "GND_A22") (pintype "power_in"))
      (node (ref "U1") (pin "AA2") (pinfunction "GND_AA2") (pintype "power_in"))
      (node (ref "U1") (pin "AA22") (pinfunction "GND_AA22") (pintype "power_in"))
      (node (ref "U1") (pin "AB1") (pinfunction "GND_AB1") (pintype "power_in"))
      (node (ref "U1") (pin "AB22") (pinfunction "GND_AB22") (pintype "power_in"))
      (node (ref "U1") (pin "AB6") (pinfunction "GND_AB6") (pintype "power_in"))
      (node (ref "U1") (pin "C11") (pinfunction "GND_C11") (pintype "power_in"))
      (node (ref "U1") (pin "C12") (pinfunction "GND_C12") (pintype "power_in"))
      (node (ref "U1") (pin "C14") (pinfunction "GND_C14") (pintype "power_in"))
      (node (ref "U1") (pin "C16") (pinfunction "GND_C16") (pintype "power_in"))
      (node (ref "U1") (pin "C18") (pinfunction "GND_C18") (pintype "power_in"))
      (node (ref "U1") (pin "C5") (pinfunction "GND_C5") (pintype "power_in"))
      (node (ref "U1") (pin "C9") (pinfunction "GND_C9") (pintype "power_in"))
      (node (ref "U1") (pin "D3") (pinfunction "GND_D3") (pintype "power_in"))
      (node (ref "U1") (pin "D8") (pinfunction "GND_D8") (pintype "power_in"))
      (node (ref "U1") (pin "E18") (pinfunction "GNDA2_E18") (pintype "power_in"))
      (node (ref "U1") (pin "E20") (pinfunction "GND_E20") (pintype "power_in"))
      (node (ref "U1") (pin "F12") (pinfunction "GND_F12") (pintype "power_in"))
      (node (ref "U1") (pin "F3") (pinfunction "GND_F3") (pintype "power_in"))
      (node (ref "U1") (pin "F5") (pinfunction "GNDA3_F5") (pintype "power_in"))
      (node (ref "U1") (pin "G2") (pinfunction "GND_G2") (pintype "power_in"))
      (node (ref "U1") (pin "G20") (pinfunction "GND_G20") (pintype "power_in"))
      (node (ref "U1") (pin "H12") (pinfunction "GND_H12") (pintype "power_in"))
      (node (ref "U1") (pin "H13") (pinfunction "GND_H13") (pintype "power_in"))
      (node (ref "U1") (pin "H3") (pinfunction "GND_H3") (pintype "power_in"))
      (node (ref "U1") (pin "J15") (pinfunction "GND_J15") (pintype "power_in"))
      (node (ref "U1") (pin "J19") (pinfunction "GND_J19") (pintype "power_in"))
      (node (ref "U1") (pin "J9") (pinfunction "GND_J9") (pintype "power_in"))
      (node (ref "U1") (pin "K10") (pinfunction "GND_K10") (pintype "power_in"))
      (node (ref "U1") (pin "K11") (pinfunction "GND_K11") (pintype "power_in"))
      (node (ref "U1") (pin "K12") (pinfunction "GND_K12") (pintype "power_in"))
      (node (ref "U1") (pin "K13") (pinfunction "GND_K13") (pintype "power_in"))
      (node (ref "U1") (pin "K16") (pinfunction "GND_K16") (pintype "power_in"))
      (node (ref "U1") (pin "K3") (pinfunction "GND_K3") (pintype "power_in"))
      (node (ref "U1") (pin "L10") (pinfunction "GND_L10") (pintype "power_in"))
      (node (ref "U1") (pin "L11") (pinfunction "GND_L11") (pintype "power_in"))
      (node (ref "U1") (pin "L12") (pinfunction "GND_L12") (pintype "power_in"))
      (node (ref "U1") (pin "L13") (pinfunction "GND_L13") (pintype "power_in"))
      (node (ref "U1") (pin "L15") (pinfunction "GND_L15") (pintype "power_in"))
      (node (ref "U1") (pin "L18") (pinfunction "MSEL1_L18") (pintype "input"))
      (node (ref "U1") (pin "L20") (pinfunction "GND_L20") (pintype "power_in"))
      (node (ref "U1") (pin "M10") (pinfunction "GND_M10") (pintype "power_in"))
      (node (ref "U1") (pin "M11") (pinfunction "GND_M11") (pintype "power_in"))
      (node (ref "U1") (pin "M12") (pinfunction "GND_M12") (pintype "power_in"))
      (node (ref "U1") (pin "M13") (pinfunction "GND_M13") (pintype "power_in"))
      (node (ref "U1") (pin "N10") (pinfunction "GND_N10") (pintype "power_in"))
      (node (ref "U1") (pin "N11") (pinfunction "GND_N11") (pintype "power_in"))
      (node (ref "U1") (pin "N12") (pinfunction "GND_N12") (pintype "power_in"))
      (node (ref "U1") (pin "N13") (pinfunction "GND_N13") (pintype "power_in"))
      (node (ref "U1") (pin "N15") (pinfunction "GND_N15") (pintype "power_in"))
      (node (ref "U1") (pin "N3") (pinfunction "GND_N3") (pintype "power_in"))
      (node (ref "U1") (pin "P19") (pinfunction "GND_P19") (pintype "power_in"))
      (node (ref "U1") (pin "P8") (pinfunction "GND_P8") (pintype "power_in"))
      (node (ref "U1") (pin "R11") (pinfunction "GND_R11") (pintype "power_in"))
      (node (ref "U1") (pin "R13") (pinfunction "GND_R13") (pintype "power_in"))
      (node (ref "U1") (pin "R3") (pinfunction "GND_R3") (pintype "power_in"))
      (node (ref "U1") (pin "R9") (pinfunction "GND_R9") (pintype "power_in"))
      (node (ref "U1") (pin "T20") (pinfunction "GND_T20") (pintype "power_in"))
      (node (ref "U1") (pin "U3") (pinfunction "GND_U3") (pintype "power_in"))
      (node (ref "U1") (pin "U5") (pinfunction "GNDA1_U5") (pintype "power_in"))
      (node (ref "U1") (pin "V18") (pinfunction "GNDA4_V18") (pintype "power_in"))
      (node (ref "U1") (pin "V20") (pinfunction "GND_V20") (pintype "power_in"))
      (node (ref "U1") (pin "W3") (pinfunction "GND_W3") (pintype "power_in"))
      (node (ref "U1") (pin "Y11") (pinfunction "GND_Y11") (pintype "power_in"))
      (node (ref "U1") (pin "Y12") (pinfunction "GND_Y12") (pintype "power_in"))
      (node (ref "U1") (pin "Y15") (pinfunction "GND_Y15") (pintype "power_in"))
      (node (ref "U1") (pin "Y16") (pinfunction "GND_Y16") (pintype "power_in"))
      (node (ref "U1") (pin "Y18") (pinfunction "GND_Y18") (pintype "power_in"))
      (node (ref "U1") (pin "Y20") (pinfunction "GND_Y20") (pintype "power_in"))
      (node (ref "U1") (pin "Y5") (pinfunction "GND_Y5") (pintype "power_in"))
      (node (ref "U1") (pin "Y9") (pinfunction "GND_Y9") (pintype "power_in"))
      (node (ref "U2") (pin "4") (pinfunction "GND_4") (pintype "power_in"))
      (node (ref "U9") (pin "3") (pinfunction "GND_3") (pintype "passive"))
      (node (ref "Y1") (pin "2") (pinfunction "GND_2") (pintype "passive"))
    )
    (net (code "23") (name "Net-(U1J-CONF_DONE)") (class "Default")
      (node (ref "R21") (pin "2") (pinfunction "2_2") (pintype "passive"))
      (node (ref "U1") (pin "M18") (pinfunction "CONF_DONE_M18") (pintype "bidirectional"))
    )
    (net (code "24") (name "Net-(U1J-nSTATUS)") (class "Default")
      (node (ref "R20") (pin "2") (pinfunction "2_2") (pintype "passive"))
      (node (ref "U1") (pin "K6") (pinfunction "nSTATUS_K6") (pintype "bidirectional"))
    )
    (net (code "25") (name "Net-(U2-DATA)") (class "Default")
      (node (ref "R22") (pin "2") (pinfunction "2_2") (pintype "passive"))
      (node (ref "R23") (pin "2") (pinfunction "2_2") (pintype "passive"))
      (node (ref "U2") (pin "2") (pinfunction "DATA_2") (pintype "output"))
    )
    (net (code "26") (name "VCC_1P2") (class "Default")
      (node (ref "C39") (pin "1") (pinfunction "1_1") (pintype "passive"))
      (node (ref "C40") (pin "1") (pinfunction "1_1") (pintype "passive"))
      (node (ref "C41") (pin "1") (pinfunction "1_1") (pintype "passive"))
      (node (ref "C42") (pin "1") (pinfunction "1_1") (pintype "passive"))
      (node (ref "C43") (pin "1") (pinfunction "1_1") (pintype "passive"))
      (node (ref "C46") (pin "1") (pinfunction "1_1") (pintype "passive"))
      (node (ref "C47") (pin "1") (pinfunction "1_1") (pintype "passive"))
      (node (ref "C48") (pin "1") (pinfunction "1_1") (pintype "passive"))
      (node (ref "C49") (pin "1") (pinfunction "1_1") (pintype "passive"))
      (node (ref "C50") (pin "1") (pinfunction "1_1") (pintype "passive"))
      (node (ref "C53") (pin "1") (pinfunction "1_1") (pintype "passive"))
      (node (ref "C54") (pin "1") (pinfunction "1_1") (pintype "passive"))
      (node (ref "C55") (pin "1") (pinfunction "1_1") (pintype "passive"))
      (node (ref "C56") (pin "1") (pinfunction "1_1") (pintype "passive"))
      (node (ref "C57") (pin "1") (pinfunction "1_1") (pintype "passive"))
      (node (ref "C60") (pin "1") (pinfunction "1_1") (pintype "passive"))
      (node (ref "C61") (pin "1") (pinfunction "1_1") (pintype "passive"))
      (node (ref "C64") (pin "1") (pinfunction "1_1") (pintype "passive"))
      (node (ref "C65") (pin "1") (pinfunction "1_1") (pintype "passive"))
      (node (ref "C68") (pin "1") (pinfunction "1_1") (pintype "passive"))
      (node (ref "C69") (pin "1") (pinfunction "1_1") (pintype "passive"))
      (node (ref "C72") (pin "1") (pinfunction "1_1") (pintype "passive"))
      (node (ref "C73") (pin "1") (pinfunction "1_1") (pintype "passive"))
      (node (ref "C76") (pin "1") (pinfunction "1_1") (pintype "passive"))
      (node (ref "C77") (pin "1") (pinfunction "1_1") (pintype "passive"))
      (node (ref "C78") (pin "1") (pinfunction "1_1") (pintype "passive"))
      (node (ref "C79") (pin "1") (pinfunction "1_1") (pintype "passive"))
      (node (ref "C80") (pin "1") (pinfunction "1_1") (pintype "passive"))
      (node (ref "FB1") (pin "1") (pinfunction "1_1") (pintype "passive"))
      (node (ref "FB2") (pin "1") (pinfunction "1_1") (pintype "passive"))
      (node (ref "FB3") (pin "1") (pinfunction "1_1") (pintype "passive"))
      (node (ref "FB4") (pin "1") (pinfunction "1_1") (pintype "passive"))
      (node (ref "U1") (pin "G12") (pinfunction "VCCINT_G12") (pintype "power_in"))
      (node (ref "U1") (pin "H9") (pinfunction "VCCINT_H9") (pintype "power_in"))
      (node (ref "U1") (pin "J10") (pinfunction "VCCINT_J10") (pintype "power_in"))
      (node (ref "U1") (pin "J11") (pinfunction "VCCINT_J11") (pintype "power_in"))
      (node (ref "U1") (pin "J12") (pinfunction "VCCINT_J12") (pintype "power_in"))
      (node (ref "U1") (pin "J13") (pinfunction "VCCINT_J13") (pintype "power_in"))
      (node (ref "U1") (pin "J14") (pinfunction "VCCINT_J14") (pintype "power_in"))
      (node (ref "U1") (pin "J16") (pinfunction "VCCINT_J16") (pintype "power_in"))
      (node (ref "U1") (pin "K14") (pinfunction "VCCINT_K14") (pintype "power_in"))
      (node (ref "U1") (pin "K15") (pinfunction "VCCINT_K15") (pintype "power_in"))
      (node (ref "U1") (pin "K9") (pinfunction "VCCINT_K9") (pintype "power_in"))
      (node (ref "U1") (pin "L14") (pinfunction "VCCINT_L14") (pintype "power_in"))
      (node (ref "U1") (pin "L16") (pinfunction "VCCINT_L16") (pintype "power_in"))
      (node (ref "U1") (pin "L9") (pinfunction "VCCINT_L9") (pintype "power_in"))
      (node (ref "U1") (pin "M14") (pinfunction "VCCINT_M14") (pintype "power_in"))
      (node (ref "U1") (pin "M15") (pinfunction "VCCINT_M15") (pintype "power_in"))
      (node (ref "U1") (pin "M9") (pinfunction "VCCINT_M9") (pintype "power_in"))
      (node (ref "U1") (pin "N14") (pinfunction "VCCINT_N14") (pintype "power_in"))
      (node (ref "U1") (pin "N9") (pinfunction "VCCINT_N9") (pintype "power_in"))
      (node (ref "U1") (pin "P10") (pinfunction "VCCINT_P10") (pintype "power_in"))
      (node (ref "U1") (pin "P11") (pinfunction "VCCINT_P11") (pintype "power_in"))
      (node (ref "U1") (pin "P12") (pinfunction "VCCINT_P12") (pintype "power_in"))
      (node (ref "U1") (pin "P13") (pinfunction "VCCINT_P13") (pintype "power_in"))
      (node (ref "U1") (pin "P14") (pinfunction "VCCINT_P14") (pintype "power_in"))
      (node (ref "U1") (pin "P9") (pinfunction "VCCINT_P9") (pintype "power_in"))
      (node (ref "U1") (pin "R10") (pinfunction "VCCINT_R10") (pintype "power_in"))
      (node (ref "U1") (pin "R12") (pinfunction "VCCINT_R12") (pintype "power_in"))
      (node (ref "U1") (pin "R8") (pinfunction "VCCINT_R8") (pintype "power_in"))
    )
    (net (code "27") (name "VCC_2P5") (class "Default")
      (node (ref "FB5") (pin "1") (pinfunction "1_1") (pintype "passive"))
      (node (ref "FB6") (pin "1") (pinfunction "1_1") (pintype "passive"))
      (node (ref "FB7") (pin "1") (pinfunction "1_1") (pintype "passive"))
      (node (ref "FB8") (pin "1") (pinfunction "1_1") (pintype "passive"))
      (node (ref "R17") (pin "2") (pinfunction "2_2") (pintype "passive"))
      (node (ref "R18") (pin "2") (pinfunction "2_2") (pintype "passive"))
    )
    (net (code "28") (name "VCC_3P3") (class "Default")
      (node (ref "C145") (pin "1") (pinfunction "1_1") (pintype "passive"))
      (node (ref "C18") (pin "1") (pinfunction "1_1") (pintype "passive"))
      (node (ref "C19") (pin "1") (pinfunction "1_1") (pintype "passive"))
      (node (ref "C20") (pin "1") (pinfunction "1_1") (pintype "passive"))
      (node (ref "C21") (pin "1") (pinfunction "1_1") (pintype "passive"))
      (node (ref "C22") (pin "1") (pinfunction "1_1") (pintype "passive"))
      (node (ref "C23") (pin "1") (pinfunction "1_1") (pintype "passive"))
      (node (ref "C24") (pin "1") (pinfunction "1_1") (pintype "passive"))
      (node (ref "C25") (pin "1") (pinfunction "1_1") (pintype "passive"))
      (node (ref "C26") (pin "1") (pinfunction "1_1") (pintype "passive"))
      (node (ref "C27") (pin "1") (pinfunction "1_1") (pintype "passive"))
      (node (ref "C28") (pin "1") (pinfunction "1_1") (pintype "passive"))
      (node (ref "C29") (pin "1") (pinfunction "1_1") (pintype "passive"))
      (node (ref "C30") (pin "1") (pinfunction "1_1") (pintype "passive"))
      (node (ref "C31") (pin "1") (pinfunction "1_1") (pintype "passive"))
      (node (ref "C32") (pin "1") (pinfunction "1_1") (pintype "passive"))
      (node (ref "C33") (pin "1") (pinfunction "1_1") (pintype "passive"))
      (node (ref "C34") (pin "1") (pinfunction "1_1") (pintype "passive"))
      (node (ref "C35") (pin "1") (pinfunction "1_1") (pintype "passive"))
      (node (ref "C36") (pin "1") (pinfunction "1_1") (pintype "passive"))
      (node (ref "C37") (pin "1") (pinfunction "1_1") (pintype "passive"))
      (node (ref "C38") (pin "1") (pinfunction "1_1") (pintype "passive"))
      (node (ref "C44") (pin "1") (pinfunction "1_1") (pintype "passive"))
      (node (ref "C45") (pin "1") (pinfunction "1_1") (pintype "passive"))
      (node (ref "C51") (pin "1") (pinfunction "1_1") (pintype "passive"))
      (node (ref "C52") (pin "1") (pinfunction "1_1") (pintype "passive"))
      (node (ref "C58") (pin "1") (pinfunction "1_1") (pintype "passive"))
      (node (ref "C59") (pin "1") (pinfunction "1_1") (pintype "passive"))
      (node (ref "C66") (pin "1") (pinfunction "1_1") (pintype "passive"))
      (node (ref "C67") (pin "1") (pinfunction "1_1") (pintype "passive"))
      (node (ref "C74") (pin "1") (pinfunction "1_1") (pintype "passive"))
      (node (ref "C75") (pin "1") (pinfunction "1_1") (pintype "passive"))
      (node (ref "C82") (pin "1") (pinfunction "1_1") (pintype "passive"))
      (node (ref "C83") (pin "1") (pinfunction "1_1") (pintype "passive"))
      (node (ref "C84") (pin "1") (pinfunction "1_1") (pintype "passive"))
      (node (ref "C85") (pin "1") (pinfunction "1_1") (pintype "passive"))
      (node (ref "C86") (pin "1") (pinfunction "1_1") (pintype "passive"))
      (node (ref "C87") (pin "1") (pinfunction "1_1") (pintype "passive"))
      (node (ref "C88") (pin "1") (pinfunction "1_1") (pintype "passive"))
      (node (ref "C89") (pin "1") (pinfunction "1_1") (pintype "passive"))
      (node (ref "C90") (pin "1") (pinfunction "1_1") (pintype "passive"))
      (node (ref "C91") (pin "1") (pinfunction "1_1") (pintype "passive"))
      (node (ref "C92") (pin "1") (pinfunction "1_1") (pintype "passive"))
      (node (ref "C93") (pin "1") (pinfunction "1_1") (pintype "passive"))
      (node (ref "C94") (pin "1") (pinfunction "1_1") (pintype "passive"))
      (node (ref "C95") (pin "1") (pinfunction "1_1") (pintype "passive"))
      (node (ref "R19") (pin "1") (pinfunction "1_1") (pintype "passive"))
      (node (ref "R20") (pin "1") (pinfunction "1_1") (pintype "passive"))
      (node (ref "R21") (pin "1") (pinfunction "1_1") (pintype "passive"))
      (node (ref "U1") (pin "A2") (pinfunction "VCCIO8_A2") (pintype "power_in"))
      (node (ref "U1") (pin "A21") (pinfunction "VCCIO7_A21") (pintype "power_in"))
      (node (ref "U1") (pin "AA6") (pinfunction "VCCIO3_AA6") (pintype "power_in"))
      (node (ref "U1") (pin "AB2") (pinfunction "VCCIO3_AB2") (pintype "power_in"))
      (node (ref "U1") (pin "AB21") (pinfunction "VCCIO4_AB21") (pintype "power_in"))
      (node (ref "U1") (pin "D11") (pinfunction "VCCIO8_D11") (pintype "power_in"))
      (node (ref "U1") (pin "D12") (pinfunction "VCCIO7_D12") (pintype "power_in"))
      (node (ref "U1") (pin "D14") (pinfunction "VCCIO7_D14") (pintype "power_in"))
      (node (ref "U1") (pin "D16") (pinfunction "VCCIO7_D16") (pintype "power_in"))
      (node (ref "U1") (pin "D18") (pinfunction "VCCIO7_D18") (pintype "power_in"))
      (node (ref "U1") (pin "D4") (pinfunction "VCCIO1_D4") (pintype "power_in"))
      (node (ref "U1") (pin "D5") (pinfunction "VCCIO8_D5") (pintype "power_in"))
      (node (ref "U1") (pin "D9") (pinfunction "VCCIO8_D9") (pintype "power_in"))
      (node (ref "U1") (pin "E19") (pinfunction "VCCIO6_E19") (pintype "power_in"))
      (node (ref "U1") (pin "E8") (pinfunction "VCCIO8_E8") (pintype "power_in"))
      (node (ref "U1") (pin "F4") (pinfunction "VCCIO1_F4") (pintype "power_in"))
      (node (ref "U1") (pin "G19") (pinfunction "VCCIO6_G19") (pintype "power_in"))
      (node (ref "U1") (pin "H4") (pinfunction "VCCIO1_H4") (pintype "power_in"))
      (node (ref "U1") (pin "J20") (pinfunction "VCCIO6_J20") (pintype "power_in"))
      (node (ref "U1") (pin "K20") (pinfunction "MSEL3_K20") (pintype "input"))
      (node (ref "U1") (pin "K4") (pinfunction "VCCIO1_K4") (pintype "power_in"))
      (node (ref "U1") (pin "L17") (pinfunction "MSEL2_L17") (pintype "input"))
      (node (ref "U1") (pin "L19") (pinfunction "VCCIO6_L19") (pintype "power_in"))
      (node (ref "U1") (pin "M17") (pinfunction "MSEL0_M17") (pintype "input"))
      (node (ref "U1") (pin "N4") (pinfunction "VCCIO2_N4") (pintype "power_in"))
      (node (ref "U1") (pin "P18") (pinfunction "VCCIO5_P18") (pintype "power_in"))
      (node (ref "U1") (pin "R4") (pinfunction "VCCIO2_R4") (pintype "power_in"))
      (node (ref "U1") (pin "T19") (pinfunction "VCCIO5_T19") (pintype "power_in"))
      (node (ref "U1") (pin "U4") (pinfunction "VCCIO2_U4") (pintype "power_in"))
      (node (ref "U1") (pin "V19") (pinfunction "VCCIO5_V19") (pintype "power_in"))
      (node (ref "U1") (pin "W11") (pinfunction "VCCIO3_W11") (pintype "power_in"))
      (node (ref "U1") (pin "W12") (pinfunction "VCCIO4_W12") (pintype "power_in"))
      (node (ref "U1") (pin "W16") (pinfunction "VCCIO4_W16") (pintype "power_in"))
      (node (ref "U1") (pin "W18") (pinfunction "VCCIO4_W18") (pintype "power_in"))
      (node (ref "U1") (pin "W4") (pinfunction "VCCIO2_W4") (pintype "power_in"))
      (node (ref "U1") (pin "W5") (pinfunction "VCCIO3_W5") (pintype "power_in"))
      (node (ref "U1") (pin "W9") (pinfunction "VCCIO3_W9") (pintype "power_in"))
      (node (ref "U1") (pin "Y14") (pinfunction "VCCIO4_Y14") (pintype "power_in"))
      (node (ref "U1") (pin "Y19") (pinfunction "VCCIO5_Y19") (pintype "power_in"))
      (node (ref "U2") (pin "3") (pinfunction "VCC_3") (pintype "power_in"))
      (node (ref "U2") (pin "7") (pinfunction "VCC_7") (pintype "power_in"))
      (node (ref "U2") (pin "8") (pinfunction "VCC_8") (pintype "power_in"))
      (node (ref "U9") (pin "5") (pinfunction "VCC_5") (pintype "passive"))
      (node (ref "Y1") (pin "4") (pinfunction "VCC_4") (pintype "passive"))
    )
    (net (code "29") (name "unconnected-(U1I-CLK1,_DIFFCLK_0n-PadG1)") (class "Default")
      (node (ref "U1") (pin "G1") (pinfunction "CLK1,_DIFFCLK_0n_G1") (pintype "input+no_connect"))
    )
    (net (code "30") (name "unconnected-(U1I-CLK2,_DIFFCLK_1p-PadT2)") (class "Default")
      (node (ref "U1") (pin "T2") (pinfunction "CLK2,_DIFFCLK_1p_T2") (pintype "input+no_connect"))
    )
    (net (code "31") (name "unconnected-(U1I-CLK4,_DIFFCLK_2p-PadG21)") (class "Default")
      (node (ref "U1") (pin "G21") (pinfunction "CLK4,_DIFFCLK_2p_G21") (pintype "input+no_connect"))
    )
    (net (code "32") (name "unconnected-(U1I-CLK5,_DIFFCLK_2n-PadG22)") (class "Default")
      (node (ref "U1") (pin "G22") (pinfunction "CLK5,_DIFFCLK_2n_G22") (pintype "input+no_connect"))
    )
    (net (code "33") (name "unconnected-(U1I-CLK6,_DIFFCLK_3p-PadT21)") (class "Default")
      (node (ref "U1") (pin "T21") (pinfunction "CLK6,_DIFFCLK_3p_T21") (pintype "input+no_connect"))
    )
    (net (code "34") (name "unconnected-(U1I-CLK7,_DIFFCLK_3n-PadT22)") (class "Default")
      (node (ref "U1") (pin "T22") (pinfunction "CLK7,_DIFFCLK_3n_T22") (pintype "input+no_connect"))
    )
    (net (code "35") (name "unconnected-(U1I-CLK8,_DIFFCLK_5n-PadA12)") (class "Default")
      (node (ref "U1") (pin "A12") (pinfunction "CLK8,_DIFFCLK_5n_A12") (pintype "input+no_connect"))
    )
    (net (code "36") (name "unconnected-(U1I-CLK9,_DIFFCLK_5p-PadB12)") (class "Default")
      (node (ref "U1") (pin "B12") (pinfunction "CLK9,_DIFFCLK_5p_B12") (pintype "input+no_connect"))
    )
    (net (code "37") (name "unconnected-(U1I-CLK10,_DIFFCLK_4n-PadA11)") (class "Default")
      (node (ref "U1") (pin "A11") (pinfunction "CLK10,_DIFFCLK_4n_A11") (pintype "input+no_connect"))
    )
    (net (code "38") (name "unconnected-(U1I-CLK11,_DIFFCLK_4p-PadB11)") (class "Default")
      (node (ref "U1") (pin "B11") (pinfunction "CLK11,_DIFFCLK_4p_B11") (pintype "input+no_connect"))
    )
    (net (code "39") (name "unconnected-(U1I-CLK12,_DIFFCLK_7n-PadAB12)") (class "Default")
      (node (ref "U1") (pin "AB12") (pinfunction "CLK12,_DIFFCLK_7n_AB12") (pintype "input+no_connect"))
    )
    (net (code "40") (name "unconnected-(U1I-CLK13,_DIFFCLK_7p-PadAA12)") (class "Default")
      (node (ref "U1") (pin "AA12") (pinfunction "CLK13,_DIFFCLK_7p_AA12") (pintype "input+no_connect"))
    )
    (net (code "41") (name "unconnected-(U1I-CLK14,_DIFFCLK_6n-PadAB11)") (class "Default")
      (node (ref "U1") (pin "AB11") (pinfunction "CLK14,_DIFFCLK_6n_AB11") (pintype "input+no_connect"))
    )
    (net (code "42") (name "unconnected-(U9-NC-Pad1)") (class "Default")
      (node (ref "U9") (pin "1") (pinfunction "NC_1") (pintype "passive"))
    )
    (net (code "43") (name "unconnected-(Y1-OE{slash}nST-Pad1)") (class "Default")
      (node (ref "Y1") (pin "1") (pinfunction "OE/nST_1") (pintype "passive"))
    )
  )
)
